# schematic.net
KiCad netlist of a schematic drawn in EAGLE
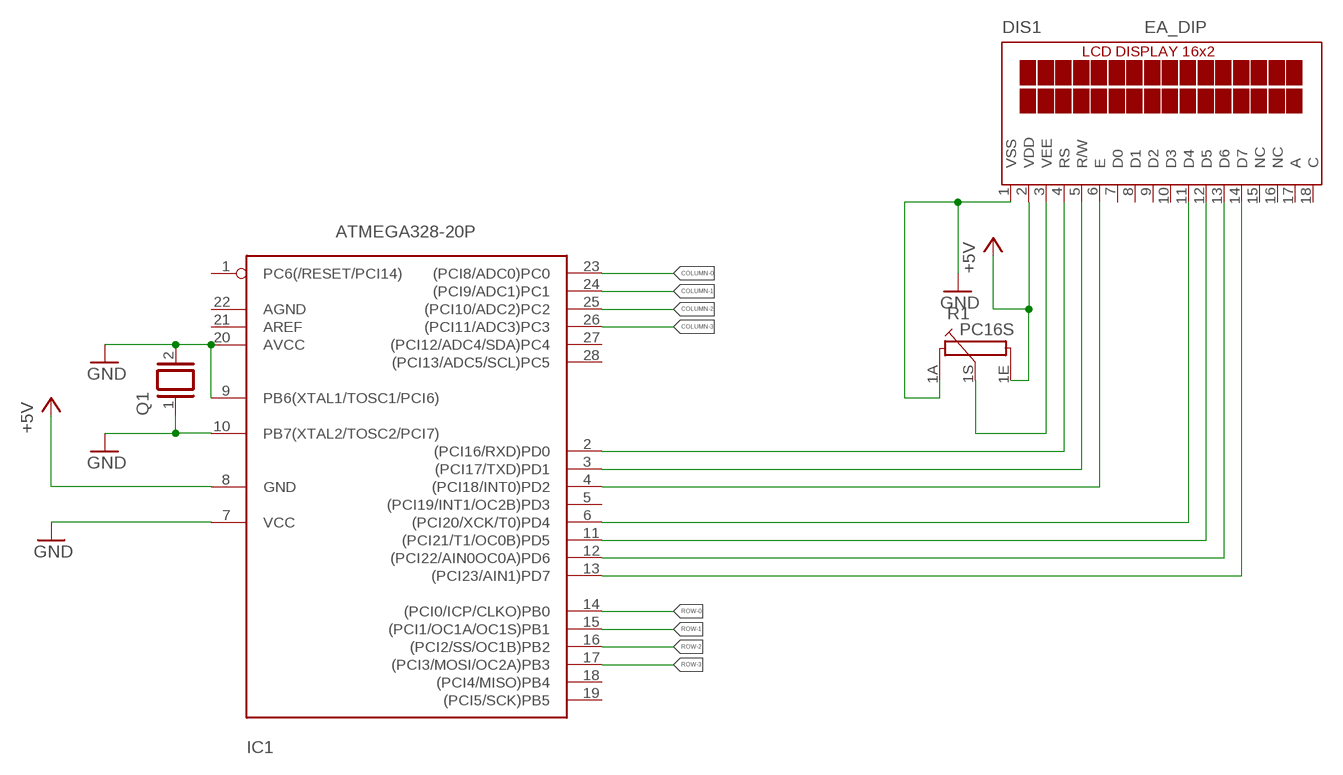
[diagram p0: schematic, sheet 1]

(export (version "E")
  (design (tool "Eeschema 10.0.6"))
  (components
    (comp (ref "DIS1")
      (value "EA_DIP")
      (footprint "eagle-import:EA_DIP")
      (libsource (lib "eagle-import") (part "EA_DIP"))
    )
    (comp (ref "IC1")
      (value "ATMEGA328-20P")
      (footprint "eagle-import:DIL28-3")
      (libsource (lib "eagle-import") (part "ATMEGA328P-20"))
    )
    (comp (ref "Q1")
      (value "XTAL")
      (footprint "eagle-import:Q")
      (libsource (lib "eagle-import") (part "XTAL"))
    )
    (comp (ref "R1")
      (value "PC16S")
      (footprint "eagle-import:PC16S")
      (libsource (lib "eagle-import") (part "PC16S"))
    )
  )
  (nets
    (net (code "1") (name "+5V") (class "Default")
      (node (ref "DIS1") (pin "2") (pinfunction "VDD_2") (pintype "power_in"))
      (node (ref "IC1") (pin "8") (pinfunction "GND_8") (pintype "bidirectional"))
      (node (ref "R1") (pin "1E") (pinfunction "1E_1E") (pintype "passive"))
    )
    (net (code "2") (name "COLUMN-0") (class "Default")
      (node (ref "IC1") (pin "23") (pinfunction "(PCI8/ADC0)PC0_23") (pintype "bidirectional"))
    )
    (net (code "3") (name "COLUMN-1") (class "Default")
      (node (ref "IC1") (pin "24") (pinfunction "(PCI9/ADC1)PC1_24") (pintype "bidirectional"))
    )
    (net (code "4") (name "COLUMN-2") (class "Default")
      (node (ref "IC1") (pin "25") (pinfunction "(PCI10/ADC2)PC2_25") (pintype "bidirectional"))
    )
    (net (code "5") (name "COLUMN-3") (class "Default")
      (node (ref "IC1") (pin "26") (pinfunction "(PCI11/ADC3)PC3_26") (pintype "bidirectional"))
    )
    (net (code "6") (name "GND") (class "Default")
      (node (ref "DIS1") (pin "1") (pinfunction "VSS_1") (pintype "power_in"))
      (node (ref "IC1") (pin "10") (pinfunction "PB7(XTAL2/TOSC2/PCI7)_10") (pintype "bidirectional"))
      (node (ref "IC1") (pin "20") (pinfunction "AVCC_20") (pintype "bidirectional"))
      (node (ref "IC1") (pin "7") (pinfunction "VCC_7") (pintype "bidirectional"))
      (node (ref "IC1") (pin "9") (pinfunction "PB6(XTAL1/TOSC1/PCI6)_9") (pintype "bidirectional"))
      (node (ref "Q1") (pin "1") (pinfunction "1_1") (pintype "passive"))
      (node (ref "Q1") (pin "2") (pinfunction "2_2") (pintype "passive"))
      (node (ref "R1") (pin "1A") (pinfunction "1A_1A") (pintype "passive"))
    )
    (net (code "7") (name "Net-(DIS1-D4)") (class "Default")
      (node (ref "DIS1") (pin "11") (pinfunction "D4_11") (pintype "input"))
      (node (ref "IC1") (pin "6") (pinfunction "(PCI20/XCK/T0)PD4_6") (pintype "bidirectional"))
    )
    (net (code "8") (name "Net-(DIS1-D5)") (class "Default")
      (node (ref "DIS1") (pin "12") (pinfunction "D5_12") (pintype "input"))
      (node (ref "IC1") (pin "11") (pinfunction "(PCI21/T1/OC0B)PD5_11") (pintype "bidirectional"))
    )
    (net (code "9") (name "Net-(DIS1-D6)") (class "Default")
      (node (ref "DIS1") (pin "13") (pinfunction "D6_13") (pintype "input"))
      (node (ref "IC1") (pin "12") (pinfunction "(PCI22/AIN0OC0A)PD6_12") (pintype "bidirectional"))
    )
    (net (code "10") (name "Net-(DIS1-D7)") (class "Default")
      (node (ref "DIS1") (pin "14") (pinfunction "D7_14") (pintype "input"))
      (node (ref "IC1") (pin "13") (pinfunction "(PCI23/AIN1)PD7_13") (pintype "bidirectional"))
    )
    (net (code "11") (name "Net-(DIS1-E)") (class "Default")
      (node (ref "DIS1") (pin "6") (pinfunction "E_6") (pintype "input"))
      (node (ref "IC1") (pin "4") (pinfunction "(PCI18/INT0)PD2_4") (pintype "bidirectional"))
    )
    (net (code "12") (name "Net-(DIS1-RS)") (class "Default")
      (node (ref "DIS1") (pin "4") (pinfunction "RS_4") (pintype "input"))
      (node (ref "IC1") (pin "2") (pinfunction "(PCI16/RXD)PD0_2") (pintype "bidirectional"))
    )
    (net (code "13") (name "Net-(DIS1-R{slash}W)") (class "Default")
      (node (ref "DIS1") (pin "5") (pinfunction "R/W_5") (pintype "input"))
      (node (ref "IC1") (pin "3") (pinfunction "(PCI17/TXD)PD1_3") (pintype "bidirectional"))
    )
    (net (code "14") (name "Net-(DIS1-VEE)") (class "Default")
      (node (ref "DIS1") (pin "3") (pinfunction "VEE_3") (pintype "power_in"))
      (node (ref "R1") (pin "1S") (pinfunction "1S_1S") (pintype "passive"))
    )
    (net (code "15") (name "ROW-0") (class "Default")
      (node (ref "IC1") (pin "14") (pinfunction "(PCI0/ICP/CLKO)PB0_14") (pintype "bidirectional"))
    )
    (net (code "16") (name "ROW-1") (class "Default")
      (node (ref "IC1") (pin "15") (pinfunction "(PCI1/OC1A/OC1S)PB1_15") (pintype "bidirectional"))
    )
    (net (code "17") (name "ROW-2") (class "Default")
      (node (ref "IC1") (pin "16") (pinfunction "(PCI2/SS/OC1B)PB2_16") (pintype "bidirectional"))
    )
    (net (code "18") (name "ROW-3") (class "Default")
      (node (ref "IC1") (pin "17") (pinfunction "(PCI3/MOSI/OC2A)PB3_17") (pintype "bidirectional"))
    )
    (net (code "19") (name "unconnected-(DIS1-A-Pad17)") (class "Default")
      (node (ref "DIS1") (pin "17") (pinfunction "A_17") (pintype "passive"))
    )
    (net (code "20") (name "unconnected-(DIS1-C-Pad18)") (class "Default")
      (node (ref "DIS1") (pin "18") (pinfunction "C_18") (pintype "passive"))
    )
    (net (code "21") (name "unconnected-(DIS1-D0-Pad7)") (class "Default")
      (node (ref "DIS1") (pin "7") (pinfunction "D0_7") (pintype "input"))
    )
    (net (code "22") (name "unconnected-(DIS1-D1-Pad8)") (class "Default")
      (node (ref "DIS1") (pin "8") (pinfunction "D1_8") (pintype "input"))
    )
    (net (code "23") (name "unconnected-(DIS1-D2-Pad9)") (class "Default")
      (node (ref "DIS1") (pin "9") (pinfunction "D2_9") (pintype "input"))
    )
    (net (code "24") (name "unconnected-(DIS1-D3-Pad10)") (class "Default")
      (node (ref "DIS1") (pin "10") (pinfunction "D3_10") (pintype "input"))
    )
    (net (code "25") (name "unconnected-(DIS1-NC-Pad15)") (class "Default")
      (node (ref "DIS1") (pin "15") (pinfunction "NC_15") (pintype "no_connect"))
    )
    (net (code "26") (name "unconnected-(DIS1-NC-Pad16)") (class "Default")
      (node (ref "DIS1") (pin "16") (pinfunction "NC_16") (pintype "no_connect"))
    )
    (net (code "27") (name "unconnected-(IC1-(PCI4{slash}MISO)PB4-Pad18)") (class "Default")
      (node (ref "IC1") (pin "18") (pinfunction "(PCI4/MISO)PB4_18") (pintype "bidirectional"))
    )
    (net (code "28") (name "unconnected-(IC1-(PCI5{slash}SCK)PB5-Pad19)") (class "Default")
      (node (ref "IC1") (pin "19") (pinfunction "(PCI5/SCK)PB5_19") (pintype "bidirectional"))
    )
    (net (code "29") (name "unconnected-(IC1-(PCI12{slash}ADC4{slash}SDA)PC4-Pad27)") (class "Default")
      (node (ref "IC1") (pin "27") (pinfunction "(PCI12/ADC4/SDA)PC4_27") (pintype "bidirectional"))
    )
    (net (code "30") (name "unconnected-(IC1-(PCI13{slash}ADC5{slash}SCL)PC5-Pad28)") (class "Default")
      (node (ref "IC1") (pin "28") (pinfunction "(PCI13/ADC5/SCL)PC5_28") (pintype "bidirectional"))
    )
    (net (code "31") (name "unconnected-(IC1-(PCI19{slash}INT1{slash}OC2B)PD3-Pad5)") (class "Default")
      (node (ref "IC1") (pin "5") (pinfunction "(PCI19/INT1/OC2B)PD3_5") (pintype "bidirectional"))
    )
    (net (code "32") (name "unconnected-(IC1-AGND-Pad22)") (class "Default")
      (node (ref "IC1") (pin "22") (pinfunction "AGND_22") (pintype "bidirectional"))
    )
    (net (code "33") (name "unconnected-(IC1-AREF-Pad21)") (class "Default")
      (node (ref "IC1") (pin "21") (pinfunction "AREF_21") (pintype "bidirectional"))
    )
    (net (code "34") (name "unconnected-(IC1-PC6({slash}RESET{slash}PCI14)-Pad1)") (class "Default")
      (node (ref "IC1") (pin "1") (pinfunction "PC6(/RESET/PCI14)_1") (pintype "bidirectional"))
    )
  )
)
